# usb.net
KiCad netlist of a schematic drawn in Altium Designer
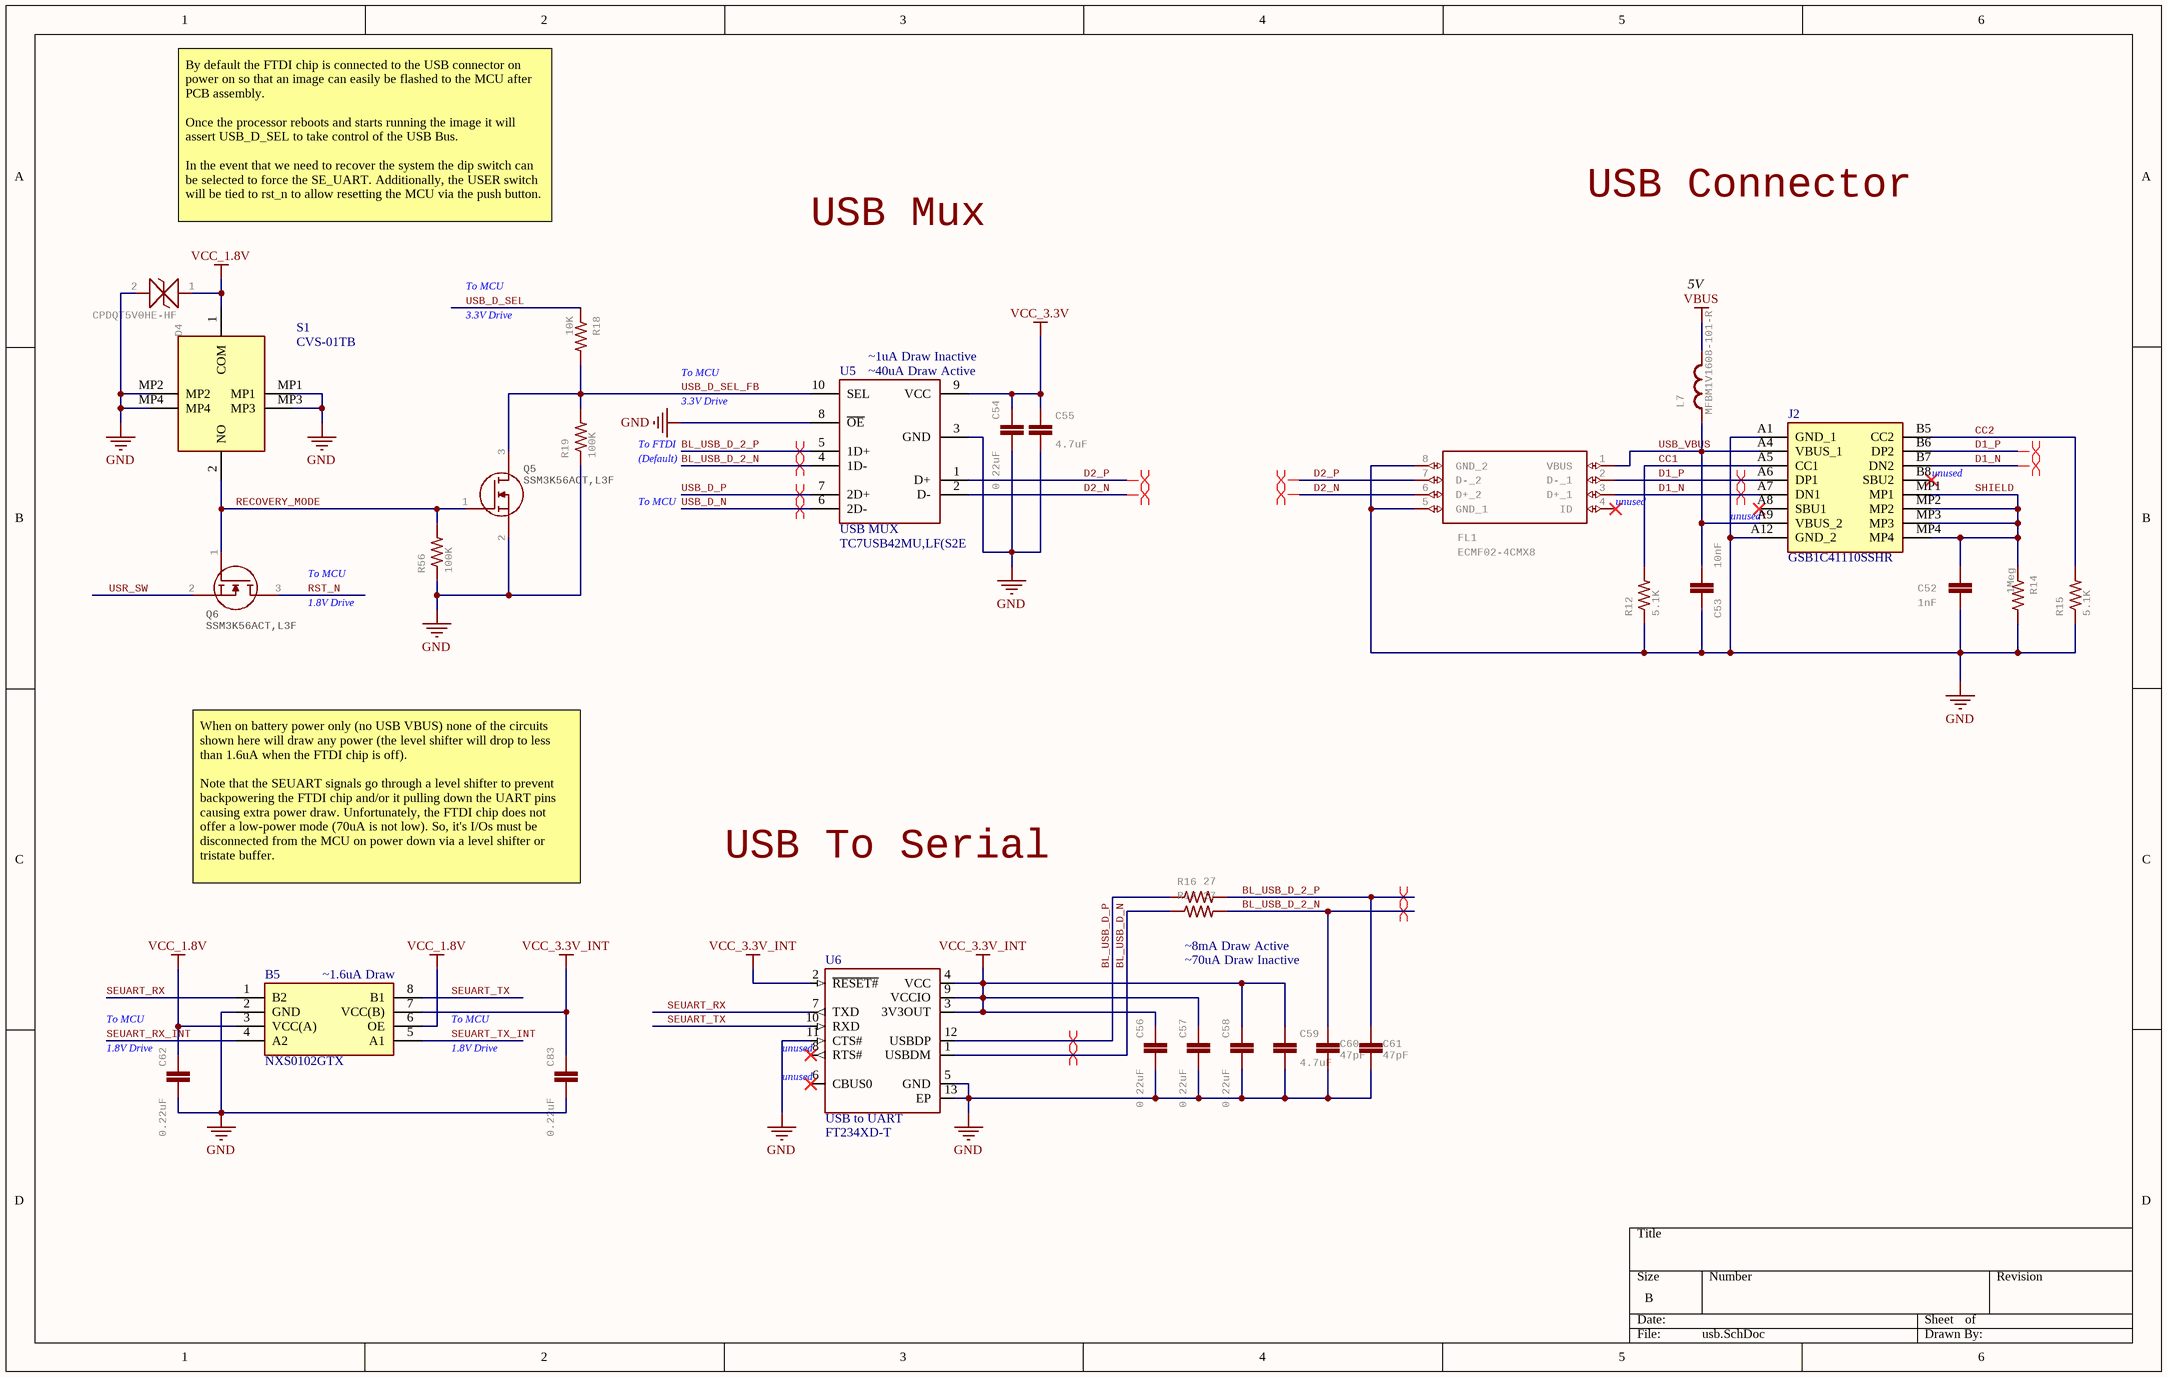
[diagram p0: usb.SchDoc]

(export (version "E")
  (design (tool "Eeschema 10.0.6"))
  (components
    (comp (ref "B5")
      (value "NXS0102GTX")
      (footprint "NXS0102GTX")
      (description "Dual supply translating transceiver; open drain; auto direction sensing")
      (fields (field (name "MOUSER PART NUMBER") "771-NXS0102GTX"))
      (libsource (lib "openmv-ae3") (part "NXS0102GTX"))
    )
    (comp (ref "C52")
      (value "1nF")
      (footprint "0402-CAP")
      (description "Capacitor")
      (fields (field (name "MPN") "VJ0402Y102JXACW1BC") (field (name "LIBRARYNAME") "sfe"))
      (libsource (lib "openmv-ae3") (part "CAP0402-CAP"))
    )
    (comp (ref "C53")
      (value "10nF")
      (footprint "0402-CAP")
      (description "CAPACITOR, European symbol")
      (fields (field (name "MPN") "0402B103K250CT"))
      (libsource (lib "openmv-ae3") (part "C-EUC0201"))
    )
    (comp (ref "C54")
      (value "0.22uF")
      (footprint "C0201")
      (description "CAPACITOR, European symbol")
      (fields (field (name "MPN") "GRM033R60J224ME15D"))
      (libsource (lib "") (part "C-EUC0201_1"))
    )
    (comp (ref "C55")
      (value "4.7uF")
      (footprint "0402-CAP")
      (description "CapacitorStandard 0603 ceramic capacitor, and 0.1\" leaded capacitor.")
      (fields (field (name "MPN") "JMK105BBJ475MV-F") (field (name "LIBRARYNAME") "sfe"))
      (libsource (lib "") (part "CAP0402-CAP_1"))
    )
    (comp (ref "C56")
      (value "0.22uF")
      (footprint "C0201")
      (description "CAPACITOR, European symbol")
      (fields (field (name "MPN") "GRM033R60J224ME15D"))
      (libsource (lib "") (part "C-EUC0201_1"))
    )
    (comp (ref "C57")
      (value "0.22uF")
      (footprint "C0201")
      (description "CAPACITOR, European symbol")
      (fields (field (name "MPN") "GRM033R60J224ME15D"))
      (libsource (lib "") (part "C-EUC0201_1"))
    )
    (comp (ref "C58")
      (value "0.22uF")
      (footprint "C0201")
      (description "CAPACITOR, European symbol")
      (fields (field (name "MPN") "GRM033R60J224ME15D"))
      (libsource (lib "") (part "C-EUC0201_1"))
    )
    (comp (ref "C59")
      (value "4.7uF")
      (footprint "0402-CAP")
      (description "CapacitorStandard 0603 ceramic capacitor, and 0.1\" leaded capacitor.")
      (fields (field (name "MPN") "JMK105BBJ475MV-F") (field (name "LIBRARYNAME") "sfe"))
      (libsource (lib "") (part "CAP0402-CAP_1"))
    )
    (comp (ref "C60")
      (value "47pF")
      (footprint "C0201")
      (description "CAPACITOR, European symbol")
      (fields (field (name "MPN") "GRM0335C1H470GA01J"))
      (libsource (lib "openmv-ae3") (part "C-EUC0201"))
    )
    (comp (ref "C61")
      (value "47pF")
      (footprint "C0201")
      (description "CAPACITOR, European symbol")
      (fields (field (name "MPN") "GRM0335C1H470GA01J"))
      (libsource (lib "openmv-ae3") (part "C-EUC0201"))
    )
    (comp (ref "C62")
      (value "0.22uF")
      (footprint "C0201")
      (description "CAPACITOR, European symbol")
      (fields (field (name "MPN") "GRM033R60J224ME15D"))
      (libsource (lib "") (part "C-EUC0201_1"))
    )
    (comp (ref "C83")
      (value "0.22uF")
      (footprint "C0201")
      (description "CAPACITOR, European symbol")
      (fields (field (name "MPN") "GRM033R60J224ME15D"))
      (libsource (lib "") (part "C-EUC0201_1"))
    )
    (comp (ref "D4")
      (value "CPDQT5V0HE-HF")
      (footprint "CPDQT5V0HEHF")
      (description "ESD Suppressors / TVS Diodes DIODE ESD 5VWM 65W 0402/SOD-923F   Source:  Datasheet")
      (fields (field (name "MOUSER_PART_NUMBER") "MOUSER_PART_NUMBER"))
      (libsource (lib "openmv-ae3") (part "CPDQT5V0HE-HF"))
    )
    (comp (ref "FL1")
      (value "ECMF02-4CMX8")
      (footprint "ECMF024CMX8")
      (fields (field (name "MOUSER_PART_NUMBER") "511-ECMF02-4CMX8"))
      (libsource (lib "openmv-ae3") (part "ECMF02-4CMX8"))
    )
    (comp (ref "J2")
      (value "GSB1C41110SSHR")
      (footprint "SamacSys:GSB1C41110SSHR")
      (description "Connector")
      (libsource (lib "openmv-ae3") (part "GSB1C41110SSHR"))
    )
    (comp (ref "L7")
      (value "MFBM1V1608-101-R")
      (footprint "0603-RES")
      (libsource (lib "openmv-ae3") (part "INDUCTOR"))
    )
    (comp (ref "Q5")
      (value "NMOS")
      (footprint "DFN1006")
      (fields (field (name "MPN") "SSM3K56ACT,L3F") (field (name "PART NUMBER") "SSM3K56ACT,L3F"))
      (libsource (lib "openmv-ae3") (part "NMOS"))
    )
    (comp (ref "Q6")
      (value "NMOS")
      (footprint "DFN1006")
      (fields (field (name "MPN") "SSM3K56ACT,L3F") (field (name "PART NUMBER") "SSM3K56ACT,L3F"))
      (libsource (lib "openmv-ae3") (part "NMOS"))
    )
    (comp (ref "R12")
      (value "5.1K")
      (footprint "R0201")
      (description "ResistorBasic schematic elements and footprints for 0603, 1206, and PTH resistors.")
      (fields (field (name "MPN") "AC0201FR-075K1L") (field (name "LIBRARYNAME") "sfe"))
      (libsource (lib "openmv-ae3") (part "RESISTOR0402-RES"))
    )
    (comp (ref "R14")
      (value "1Meg")
      (footprint "0402-RES")
      (description "Resistor")
      (fields (field (name "MPN") "CRCW04021M00FKEDC") (field (name "LIBRARYNAME") "sfe"))
      (libsource (lib "openmv-ae3") (part "RESISTOR0402-RES"))
    )
    (comp (ref "R15")
      (value "5.1K")
      (footprint "R0201")
      (description "ResistorBasic schematic elements and footprints for 0603, 1206, and PTH resistors.")
      (fields (field (name "MPN") "AC0201FR-075K1L") (field (name "LIBRARYNAME") "sfe"))
      (libsource (lib "openmv-ae3") (part "RESISTOR0402-RES"))
    )
    (comp (ref "R16")
      (value "27")
      (footprint "R0201")
      (fields (field (name "MPN") "RC0201JR-0727RL") (field (name "LIBRARYNAME") "sfe"))
      (libsource (lib "openmv-ae3") (part "RESISTOR0402-RES"))
    )
    (comp (ref "R17")
      (value "27")
      (footprint "R0201")
      (fields (field (name "MPN") "RC0201JR-0727RL") (field (name "LIBRARYNAME") "sfe"))
      (libsource (lib "openmv-ae3") (part "RESISTOR0402-RES"))
    )
    (comp (ref "R18")
      (value "10K")
      (footprint "R0201")
      (fields (field (name "MPN") "RMCF0201FT10K0") (field (name "LIBRARYNAME") "sfe"))
      (libsource (lib "openmv-ae3") (part "RESISTOR0402-RES"))
    )
    (comp (ref "R19")
      (value "100K")
      (footprint "R0201")
      (fields (field (name "MPN") "RMCF0201FT100K") (field (name "LIBRARYNAME") "sfe"))
      (libsource (lib "openmv-ae3") (part "RESISTOR0402-RES"))
    )
    (comp (ref "R56")
      (value "100K")
      (footprint "R0201")
      (fields (field (name "MPN") "RMCF0201FT100K") (field (name "LIBRARYNAME") "sfe"))
      (libsource (lib "openmv-ae3") (part "RESISTOR0402-RES"))
    )
    (comp (ref "S1")
      (value "CVS-01TB")
      (footprint "SamacSys:CVS01TB")
      (description "Switch")
      (fields (field (name "MOUSER PART NUMBER") "229-CVS-01TB"))
      (libsource (lib "openmv-ae3") (part "CVS-01TB"))
    )
    (comp (ref "U5")
      (value "USB MUX")
      (footprint "TC7USB42MU,LF(S2E")
      (fields
        (field (name "MF") "Toshiba")
        (field (name "MPN") "TC7USB42MU,LF(S2E")
        (field (name "PART NUMBER") "TC7USB42MU,LF(S2E")
      )
      (libsource (lib "openmv-ae3") (part "TC7USB42MU,LF(S2E"))
    )
    (comp (ref "U6")
      (value "USB to UART")
      (footprint "SON45P300X300X80-13N")
      (description "USB Bridge, USB to UART USB 2.0 UART Interface 12-DFN _3x3_")
      (fields
        (field (name "MF") "FTDI,")
        (field (name "PART NUMBER") "FT234XD-T")
        (field (name "MPN") "FT234XD-T")
      )
      (libsource (lib "openmv-ae3") (part "FT234XD-T"))
    )
  )
  (nets
    (net (code "1") (name "/BL_USB_D_2_N") (class "Default")
      (node (ref "C60") (pin "2") (pinfunction "2_2") (pintype "passive"))
      (node (ref "R17") (pin "2") (pinfunction "2_2") (pintype "passive"))
      (node (ref "U5") (pin "4") (pinfunction "1D-_4") (pintype "passive"))
    )
    (net (code "2") (name "/BL_USB_D_2_P") (class "Default")
      (node (ref "C61") (pin "2") (pinfunction "2_2") (pintype "passive"))
      (node (ref "R16") (pin "2") (pinfunction "2_2") (pintype "passive"))
      (node (ref "U5") (pin "5") (pinfunction "1D+_5") (pintype "passive"))
    )
    (net (code "3") (name "/BL_USB_D_N") (class "Default")
      (node (ref "R17") (pin "1") (pinfunction "1_1") (pintype "passive"))
      (node (ref "U6") (pin "1") (pinfunction "USBDM_1") (pintype "bidirectional"))
    )
    (net (code "4") (name "/BL_USB_D_P") (class "Default")
      (node (ref "R16") (pin "1") (pinfunction "1_1") (pintype "passive"))
      (node (ref "U6") (pin "12") (pinfunction "USBDP_12") (pintype "bidirectional"))
    )
    (net (code "5") (name "/CC1") (class "Default")
      (node (ref "J2") (pin "A5") (pinfunction "CC1_A5") (pintype "passive"))
      (node (ref "R12") (pin "2") (pinfunction "2_2") (pintype "passive"))
    )
    (net (code "6") (name "/CC2") (class "Default")
      (node (ref "J2") (pin "B5") (pinfunction "CC2_B5") (pintype "passive"))
      (node (ref "R15") (pin "2") (pinfunction "2_2") (pintype "passive"))
    )
    (net (code "7") (name "/D1_N") (class "Default")
      (node (ref "FL1") (pin "3") (pinfunction "D+_1_3") (pintype "bidirectional"))
      (node (ref "J2") (pin "A7") (pinfunction "DN1_A7") (pintype "passive"))
      (node (ref "J2") (pin "B7") (pinfunction "DN2_B7") (pintype "passive"))
    )
    (net (code "8") (name "/D1_P") (class "Default")
      (node (ref "FL1") (pin "2") (pinfunction "D-_1_2") (pintype "bidirectional"))
      (node (ref "J2") (pin "A6") (pinfunction "DP1_A6") (pintype "passive"))
      (node (ref "J2") (pin "B6") (pinfunction "DP2_B6") (pintype "passive"))
    )
    (net (code "9") (name "/D2_N") (class "Default")
      (node (ref "FL1") (pin "6") (pinfunction "D+_2_6") (pintype "bidirectional"))
      (node (ref "U5") (pin "2") (pinfunction "D-_2") (pintype "passive"))
    )
    (net (code "10") (name "/D2_P") (class "Default")
      (node (ref "FL1") (pin "7") (pinfunction "D-_2_7") (pintype "bidirectional"))
      (node (ref "U5") (pin "1") (pinfunction "D+_1") (pintype "passive"))
    )
    (net (code "11") (name "/RECOVERY_MODE") (class "Default")
      (node (ref "Q5") (pin "1") (pinfunction "G_1") (pintype "bidirectional"))
      (node (ref "Q6") (pin "1") (pinfunction "G_1") (pintype "bidirectional"))
      (node (ref "R56") (pin "2") (pinfunction "2_2") (pintype "passive"))
      (node (ref "S1") (pin "2") (pinfunction "NO_2") (pintype "passive"))
    )
    (net (code "12") (name "/RST_N") (class "Default")
      (node (ref "Q6") (pin "3") (pinfunction "D_3") (pintype "bidirectional"))
    )
    (net (code "13") (name "/SEUART_RX") (class "Default")
      (node (ref "B5") (pin "1") (pinfunction "B2_1") (pintype "passive"))
      (node (ref "U6") (pin "7") (pinfunction "TXD_7") (pintype "output"))
    )
    (net (code "14") (name "/SEUART_RX_INT") (class "Default")
      (node (ref "B5") (pin "4") (pinfunction "A2_4") (pintype "passive"))
    )
    (net (code "15") (name "/SEUART_TX") (class "Default")
      (node (ref "B5") (pin "8") (pinfunction "B1_8") (pintype "passive"))
      (node (ref "U6") (pin "10") (pinfunction "RXD_10") (pintype "input"))
    )
    (net (code "16") (name "/SEUART_TX_INT") (class "Default")
      (node (ref "B5") (pin "5") (pinfunction "A1_5") (pintype "passive"))
    )
    (net (code "17") (name "/SHIELD") (class "Default")
      (node (ref "C52") (pin "1") (pinfunction "1_1") (pintype "passive"))
      (node (ref "J2") (pin "MP1") (pinfunction "MP1_MP1") (pintype "passive"))
      (node (ref "J2") (pin "MP2") (pinfunction "MP2_MP2") (pintype "passive"))
      (node (ref "J2") (pin "MP3") (pinfunction "MP3_MP3") (pintype "passive"))
      (node (ref "J2") (pin "MP4") (pinfunction "MP4_MP4") (pintype "passive"))
      (node (ref "R14") (pin "1") (pinfunction "1_1") (pintype "passive"))
    )
    (net (code "18") (name "/USB_D_N") (class "Default")
      (node (ref "U5") (pin "6") (pinfunction "2D-_6") (pintype "passive"))
    )
    (net (code "19") (name "/USB_D_P") (class "Default")
      (node (ref "U5") (pin "7") (pinfunction "2D+_7") (pintype "passive"))
    )
    (net (code "20") (name "/USB_D_SEL") (class "Default")
      (node (ref "R18") (pin "1") (pinfunction "1_1") (pintype "passive"))
    )
    (net (code "21") (name "/USB_D_SEL_FB") (class "Default")
      (node (ref "Q5") (pin "3") (pinfunction "D_3") (pintype "bidirectional"))
      (node (ref "R18") (pin "2") (pinfunction "2_2") (pintype "passive"))
      (node (ref "R19") (pin "2") (pinfunction "2_2") (pintype "passive"))
      (node (ref "U5") (pin "10") (pinfunction "SEL_10") (pintype "passive"))
    )
    (net (code "22") (name "/USB_VBUS") (class "Default")
      (node (ref "C53") (pin "2") (pinfunction "2_2") (pintype "passive"))
      (node (ref "FL1") (pin "1") (pinfunction "VBUS_1") (pintype "bidirectional"))
      (node (ref "J2") (pin "A4") (pinfunction "VBUS_1_A4") (pintype "passive"))
      (node (ref "J2") (pin "A9") (pinfunction "VBUS_2_A9") (pintype "passive"))
      (node (ref "L7") (pin "1") (pinfunction "1_1") (pintype "passive"))
    )
    (net (code "23") (name "/USR_SW") (class "Default")
      (node (ref "Q6") (pin "2") (pinfunction "S_2") (pintype "bidirectional"))
    )
    (net (code "24") (name "GND") (class "Default")
      (node (ref "B5") (pin "2") (pinfunction "GND_2") (pintype "passive"))
      (node (ref "C52") (pin "2") (pinfunction "2_2") (pintype "passive"))
      (node (ref "C53") (pin "1") (pinfunction "1_1") (pintype "passive"))
      (node (ref "C54") (pin "2") (pinfunction "2_2") (pintype "passive"))
      (node (ref "C55") (pin "1") (pinfunction "1_1") (pintype "passive"))
      (node (ref "C56") (pin "2") (pinfunction "2_2") (pintype "passive"))
      (node (ref "C57") (pin "2") (pinfunction "2_2") (pintype "passive"))
      (node (ref "C58") (pin "2") (pinfunction "2_2") (pintype "passive"))
      (node (ref "C59") (pin "1") (pinfunction "1_1") (pintype "passive"))
      (node (ref "C60") (pin "1") (pinfunction "1_1") (pintype "passive"))
      (node (ref "C61") (pin "1") (pinfunction "1_1") (pintype "passive"))
      (node (ref "C62") (pin "2") (pinfunction "2_2") (pintype "passive"))
      (node (ref "C83") (pin "2") (pinfunction "2_2") (pintype "passive"))
      (node (ref "D4") (pin "2") (pinfunction "2_2") (pintype "bidirectional"))
      (node (ref "FL1") (pin "5") (pinfunction "GND_1_5") (pintype "bidirectional"))
      (node (ref "FL1") (pin "8") (pinfunction "GND_2_8") (pintype "bidirectional"))
      (node (ref "J2") (pin "A1") (pinfunction "GND_1_A1") (pintype "passive"))
      (node (ref "J2") (pin "A12") (pinfunction "GND_2_A12") (pintype "passive"))
      (node (ref "Q5") (pin "2") (pinfunction "S_2") (pintype "bidirectional"))
      (node (ref "R12") (pin "1") (pinfunction "1_1") (pintype "passive"))
      (node (ref "R14") (pin "2") (pinfunction "2_2") (pintype "passive"))
      (node (ref "R15") (pin "1") (pinfunction "1_1") (pintype "passive"))
      (node (ref "R19") (pin "1") (pinfunction "1_1") (pintype "passive"))
      (node (ref "R56") (pin "1") (pinfunction "1_1") (pintype "passive"))
      (node (ref "S1") (pin "MP1") (pinfunction "MP1_MP1") (pintype "passive"))
      (node (ref "S1") (pin "MP2") (pinfunction "MP2_MP2") (pintype "passive"))
      (node (ref "S1") (pin "MP3") (pinfunction "MP3_MP3") (pintype "passive"))
      (node (ref "S1") (pin "MP4") (pinfunction "MP4_MP4") (pintype "passive"))
      (node (ref "U5") (pin "3") (pinfunction "GND_3") (pintype "passive"))
      (node (ref "U5") (pin "8") (pinfunction "~{OE}_8") (pintype "passive"))
      (node (ref "U6") (pin "11") (pinfunction "CTS#_11") (pintype "input"))
      (node (ref "U6") (pin "13") (pinfunction "EP_13") (pintype "power_in"))
      (node (ref "U6") (pin "5") (pinfunction "GND_5") (pintype "power_in"))
    )
    (net (code "25") (name "VBUS") (class "Default")
      (node (ref "L7") (pin "2") (pinfunction "2_2") (pintype "passive"))
    )
    (net (code "26") (name "VCC_1.8V") (class "Default")
      (node (ref "B5") (pin "3") (pinfunction "VCC(A)_3") (pintype "passive"))
      (node (ref "B5") (pin "6") (pinfunction "OE_6") (pintype "passive"))
      (node (ref "C62") (pin "1") (pinfunction "1_1") (pintype "passive"))
      (node (ref "D4") (pin "1") (pinfunction "1_1") (pintype "bidirectional"))
      (node (ref "S1") (pin "1") (pinfunction "COM_1") (pintype "passive"))
    )
    (net (code "27") (name "VCC_3.3V") (class "Default")
      (node (ref "C54") (pin "1") (pinfunction "1_1") (pintype "passive"))
      (node (ref "C55") (pin "2") (pinfunction "2_2") (pintype "passive"))
      (node (ref "U5") (pin "9") (pinfunction "VCC_9") (pintype "passive"))
    )
    (net (code "28") (name "VCC_3.3V_INT") (class "Default")
      (node (ref "B5") (pin "7") (pinfunction "VCC(B)_7") (pintype "passive"))
      (node (ref "C56") (pin "1") (pinfunction "1_1") (pintype "passive"))
      (node (ref "C57") (pin "1") (pinfunction "1_1") (pintype "passive"))
      (node (ref "C58") (pin "1") (pinfunction "1_1") (pintype "passive"))
      (node (ref "C59") (pin "2") (pinfunction "2_2") (pintype "passive"))
      (node (ref "C83") (pin "1") (pinfunction "1_1") (pintype "passive"))
      (node (ref "U6") (pin "2") (pinfunction "~{RESET#}_2") (pintype "input"))
      (node (ref "U6") (pin "3") (pinfunction "3V3OUT_3") (pintype "power_in"))
      (node (ref "U6") (pin "4") (pinfunction "VCC_4") (pintype "power_in"))
      (node (ref "U6") (pin "9") (pinfunction "VCCIO_9") (pintype "power_in"))
    )
    (net (code "29") (name "unconnected-(FL1-ID-Pad4)") (class "Default")
      (node (ref "FL1") (pin "4") (pinfunction "ID_4") (pintype "bidirectional+no_connect"))
    )
    (net (code "30") (name "unconnected-(J2-SBU1-PadA8)") (class "Default")
      (node (ref "J2") (pin "A8") (pinfunction "SBU1_A8") (pintype "passive+no_connect"))
    )
    (net (code "31") (name "unconnected-(J2-SBU2-PadB8)") (class "Default")
      (node (ref "J2") (pin "B8") (pinfunction "SBU2_B8") (pintype "passive+no_connect"))
    )
    (net (code "32") (name "unconnected-(U6-CBUS0-Pad6)") (class "Default")
      (node (ref "U6") (pin "6") (pinfunction "CBUS0_6") (pintype "bidirectional+no_connect"))
    )
    (net (code "33") (name "unconnected-(U6-RTS#-Pad8)") (class "Default")
      (node (ref "U6") (pin "8") (pinfunction "RTS#_8") (pintype "output+no_connect"))
    )
  )
)
